# 2025_08_24_leds.net
KiCad netlist of a schematic drawn in EasyEDA Pro
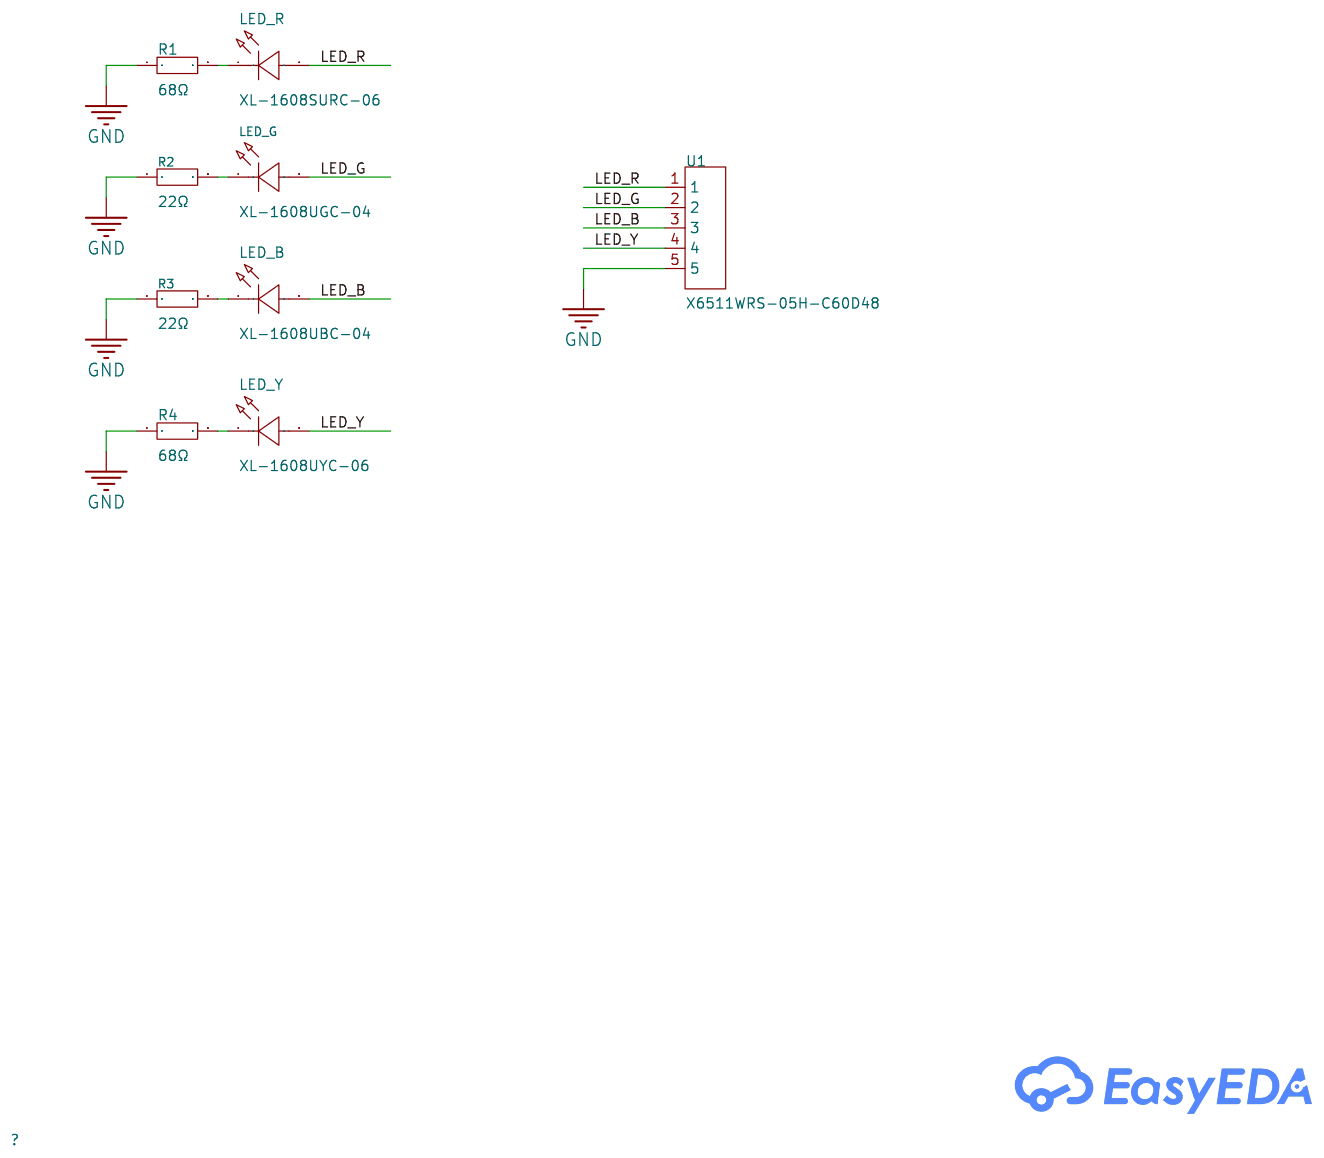
[diagram p0: schematic sheet]

(export (version "E")
  (design (tool "Eeschema 10.0.6"))
  (components
    (comp (ref "LED_B")
      (value "XL-1608UBC-04")
      (footprint "easyedapro:LED0603-RD_BLUE")
      (fields (field (name "Manufacturer") "XINGLIGHT(成兴光)"))
      (libsource (lib "easyedapro") (part "XL-1608UBC-04"))
    )
    (comp (ref "LED_G")
      (value "XL-1608UGC-04")
      (footprint "easyedapro:LED0603-RD_GREEN")
      (fields (field (name "Manufacturer") "XINGLIGHT(成兴光)"))
      (libsource (lib "easyedapro") (part "XL-1608UGC-04"))
    )
    (comp (ref "LED_R")
      (value "XL-1608SURC-06")
      (footprint "easyedapro:LED0603-RD_RED")
      (fields (field (name "Manufacturer") "XINGLIGHT(成兴光)"))
      (libsource (lib "easyedapro") (part "XL-1608SURC-06"))
    )
    (comp (ref "LED_Y")
      (value "XL-1608UYC-06")
      (footprint "easyedapro:LED0603-RD-YELLOW")
      (fields (field (name "Manufacturer") "XINGLIGHT(成兴光)"))
      (libsource (lib "easyedapro") (part "XL-1608UYC-06"))
    )
    (comp (ref "R1")
      (value "68Ω")
      (footprint "easyedapro:R0402")
      (fields (field (name "Manufacturer Part") "RC0402FR-0768RL") (field (name "Manufacturer") "YAGEO(国巨)"))
      (libsource (lib "easyedapro") (part "RC0402FR-0768RL"))
    )
    (comp (ref "R2")
      (value "22Ω")
      (footprint "easyedapro:R0402")
      (fields
        (field (name "Manufacturer Part") "0402WGF220JTCE")
        (field (name "Manufacturer") "UNI-ROYAL(厚声)")
      )
      (libsource (lib "easyedapro") (part "0402WGF220JTCE"))
    )
    (comp (ref "R3")
      (value "22Ω")
      (footprint "easyedapro:R0402")
      (fields
        (field (name "Manufacturer Part") "0402WGF220JTCE")
        (field (name "Manufacturer") "UNI-ROYAL(厚声)")
      )
      (libsource (lib "easyedapro") (part "0402WGF220JTCE"))
    )
    (comp (ref "R4")
      (value "68Ω")
      (footprint "easyedapro:R0402")
      (fields (field (name "Manufacturer Part") "RC0402FR-0768RL") (field (name "Manufacturer") "YAGEO(国巨)"))
      (libsource (lib "easyedapro") (part "RC0402FR-0768RL"))
    )
    (comp (ref "U1")
      (value "X6511WRS-05H-C60D48")
      (footprint "easyedapro:HDR-SMD_5P-P2.54-H-M-W13.3-N")
      (fields (field (name "Manufacturer") "XKB Connection(中国星坤)"))
      (libsource (lib "easyedapro") (part "X6511WRS-05H-C60D48"))
    )
  )
  (nets
    (net (code "1") (name "/LED_B") (class "Default")
      (node (ref "LED_B") (pin "2") (pinfunction "A_2") (pintype "unspecified"))
      (node (ref "U1") (pin "3") (pinfunction "3_3") (pintype "unspecified"))
    )
    (net (code "2") (name "/LED_G") (class "Default")
      (node (ref "LED_G") (pin "2") (pinfunction "A_2") (pintype "input"))
      (node (ref "U1") (pin "2") (pinfunction "2_2") (pintype "unspecified"))
    )
    (net (code "3") (name "/LED_R") (class "Default")
      (node (ref "LED_R") (pin "2") (pinfunction "A_2") (pintype "unspecified"))
      (node (ref "U1") (pin "1") (pinfunction "1_1") (pintype "unspecified"))
    )
    (net (code "4") (name "/LED_Y") (class "Default")
      (node (ref "LED_Y") (pin "2") (pinfunction "A_2") (pintype "unspecified"))
      (node (ref "U1") (pin "4") (pinfunction "4_4") (pintype "unspecified"))
    )
    (net (code "5") (name "GND") (class "Default")
      (node (ref "R1") (pin "1") (pinfunction "1_1") (pintype "input"))
      (node (ref "R2") (pin "1") (pinfunction "1_1") (pintype "input"))
      (node (ref "R3") (pin "1") (pinfunction "1_1") (pintype "input"))
      (node (ref "R4") (pin "1") (pinfunction "1_1") (pintype "input"))
      (node (ref "U1") (pin "5") (pinfunction "5_5") (pintype "unspecified"))
    )
    (net (code "6") (name "Net-(LED_B-K)") (class "Default")
      (node (ref "LED_B") (pin "1") (pinfunction "K_1") (pintype "unspecified"))
      (node (ref "R3") (pin "2") (pinfunction "2_2") (pintype "input"))
    )
    (net (code "7") (name "Net-(LED_G-K)") (class "Default")
      (node (ref "LED_G") (pin "1") (pinfunction "K_1") (pintype "input"))
      (node (ref "R2") (pin "2") (pinfunction "2_2") (pintype "input"))
    )
    (net (code "8") (name "Net-(LED_R-K)") (class "Default")
      (node (ref "LED_R") (pin "1") (pinfunction "K_1") (pintype "unspecified"))
      (node (ref "R1") (pin "2") (pinfunction "2_2") (pintype "input"))
    )
    (net (code "9") (name "Net-(LED_Y-K)") (class "Default")
      (node (ref "LED_Y") (pin "1") (pinfunction "K_1") (pintype "unspecified"))
      (node (ref "R4") (pin "2") (pinfunction "2_2") (pintype "input"))
    )
  )
)
